# RH025_1.net
KiCad netlist of a schematic drawn in EAGLE
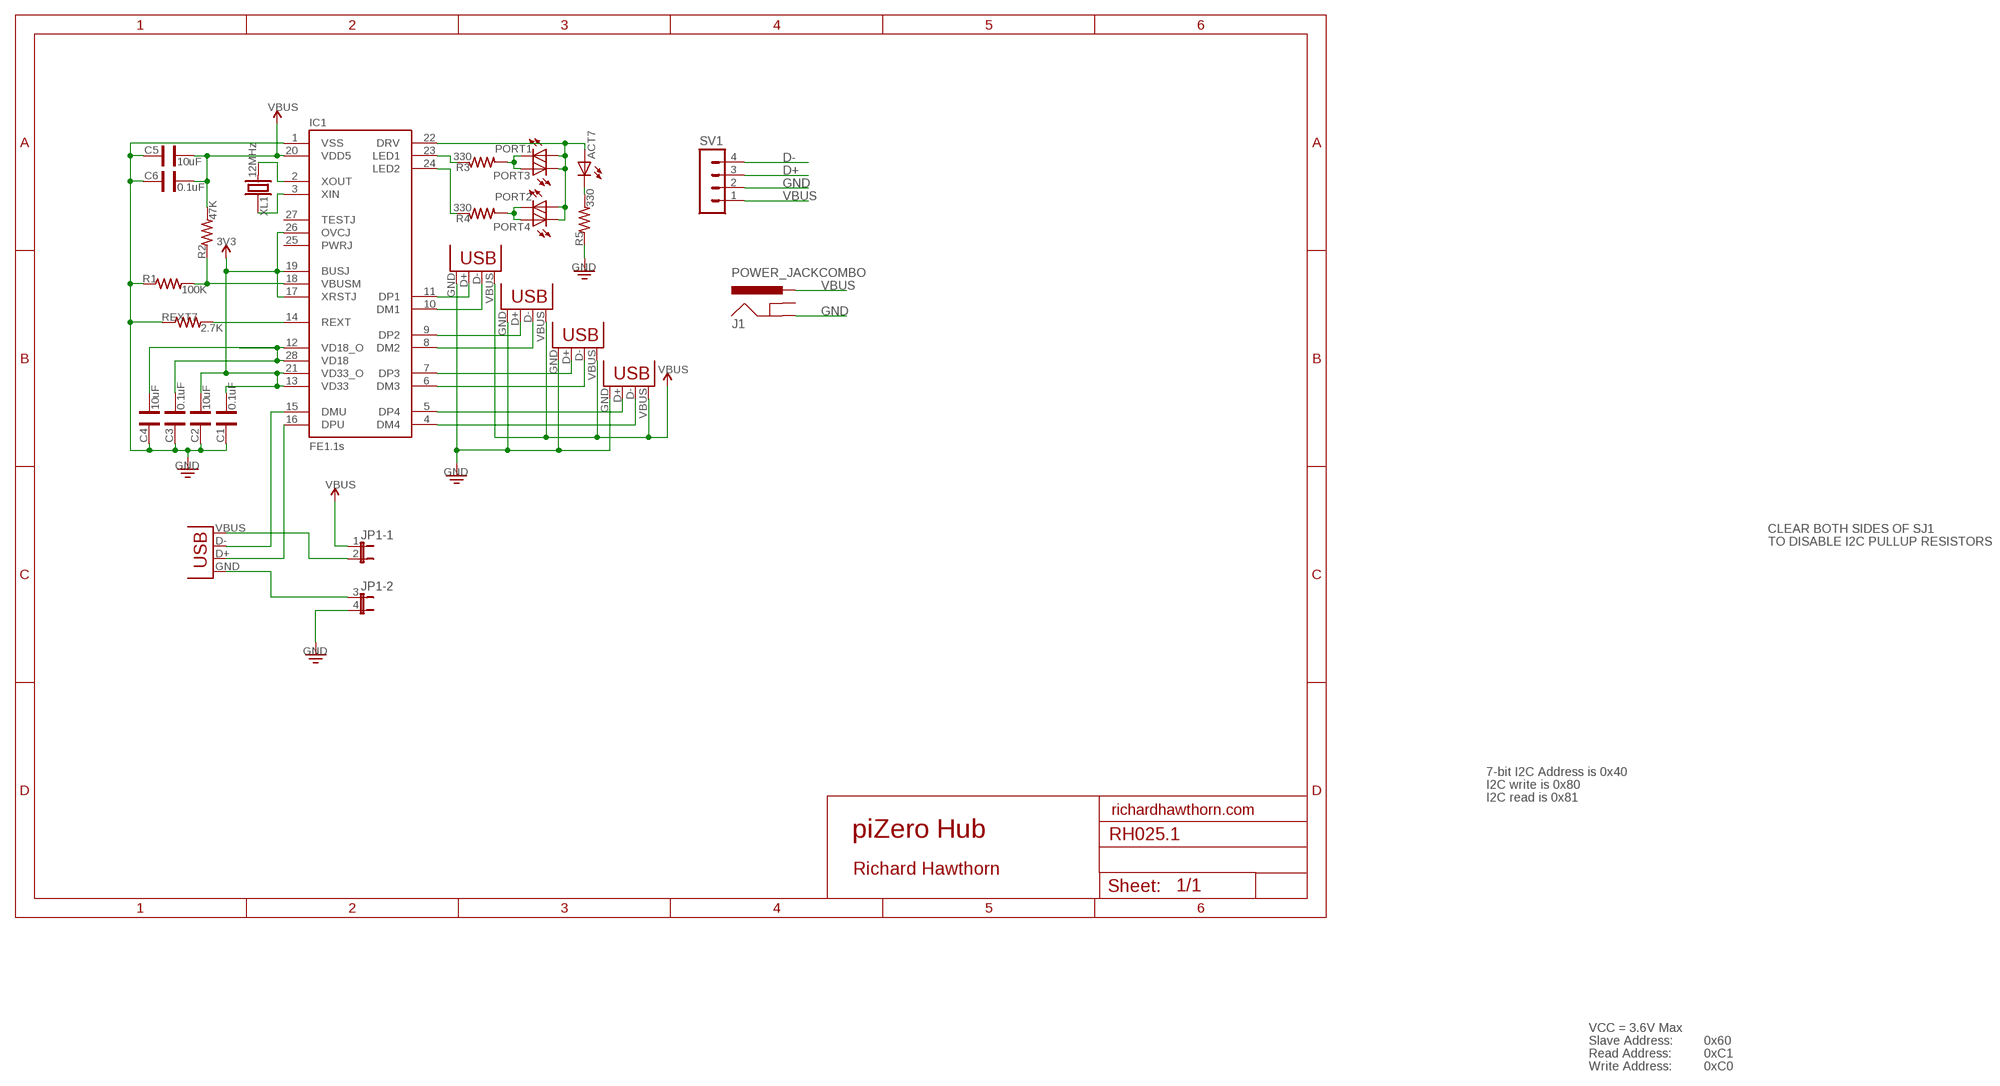
[diagram p0: schematic, sheet 1]

(export (version "E")
  (design (tool "Eeschema 10.0.6"))
  (components
    (comp (ref "ACT7")
      (value "LED0603")
      (footprint "eagle-import:LED-0603")
      (libsource (lib "eagle-import") (part "LED0603"))
    )
    (comp (ref "C1")
      (value "0.1uF")
      (footprint "eagle-import:CAP-0603")
      (libsource (lib "eagle-import") (part "CAP0603"))
    )
    (comp (ref "C2")
      (value "10uF")
      (footprint "eagle-import:CAP-0603")
      (libsource (lib "eagle-import") (part "CAP0603"))
    )
    (comp (ref "C3")
      (value "0.1uF")
      (footprint "eagle-import:CAP-0603")
      (libsource (lib "eagle-import") (part "CAP0603"))
    )
    (comp (ref "C4")
      (value "10uF")
      (footprint "eagle-import:CAP-0603")
      (libsource (lib "eagle-import") (part "CAP0603"))
    )
    (comp (ref "C5")
      (value "10uF")
      (footprint "eagle-import:CAP-0603")
      (libsource (lib "eagle-import") (part "CAP0603"))
    )
    (comp (ref "C6")
      (value "0.1uF")
      (footprint "eagle-import:CAP-0603")
      (libsource (lib "eagle-import") (part "CAP0603"))
    )
    (comp (ref "IC1")
      (value "FE1.1S")
      (footprint "eagle-import:FE1.1S_SSOP-28")
      (libsource (lib "eagle-import") (part "FE1.1S"))
    )
    (comp (ref "J1")
      (value "POWER_JACKCOMBO")
      (footprint "eagle-import:POWER_JACK_COMBO")
      (libsource (lib "eagle-import") (part "POWER_JACKCOMBO"))
    )
    (comp (ref "JP1")
      (value "JP2QE")
      (footprint "eagle-import:JP2Q")
      (libsource (lib "eagle-import") (part "JP2QE"))
    )
    (comp (ref "PORT1")
      (value "LED0603")
      (footprint "eagle-import:LED-0603")
      (libsource (lib "eagle-import") (part "LED0603"))
    )
    (comp (ref "PORT2")
      (value "LED0603")
      (footprint "eagle-import:LED-0603")
      (libsource (lib "eagle-import") (part "LED0603"))
    )
    (comp (ref "PORT3")
      (value "LED0603")
      (footprint "eagle-import:LED-0603")
      (libsource (lib "eagle-import") (part "LED0603"))
    )
    (comp (ref "PORT4")
      (value "LED0603")
      (footprint "eagle-import:LED-0603")
      (libsource (lib "eagle-import") (part "LED0603"))
    )
    (comp (ref "R1")
      (value "100K")
      (footprint "eagle-import:RES-0603")
      (libsource (lib "eagle-import") (part "RES0603"))
    )
    (comp (ref "R2")
      (value "47K")
      (footprint "eagle-import:RES-0603")
      (libsource (lib "eagle-import") (part "RES0603"))
    )
    (comp (ref "R3")
      (value "330")
      (footprint "eagle-import:RES-0603")
      (libsource (lib "eagle-import") (part "RES0603"))
    )
    (comp (ref "R4")
      (value "330")
      (footprint "eagle-import:RES-0603")
      (libsource (lib "eagle-import") (part "RES0603"))
    )
    (comp (ref "R5")
      (value "330")
      (footprint "eagle-import:RES-0603")
      (libsource (lib "eagle-import") (part "RES0603"))
    )
    (comp (ref "REXT7")
      (value "2.7K")
      (footprint "eagle-import:RES-0603")
      (libsource (lib "eagle-import") (part "RES0603"))
    )
    (comp (ref "SV1")
      (value "MA04-1")
      (footprint "eagle-import:MA04-1")
      (libsource (lib "eagle-import") (part "MA04-1"))
    )
    (comp (ref "USB1")
      (value "USBMICROB-PTH")
      (footprint "eagle-import:USB-MICROB-TH")
      (libsource (lib "eagle-import") (part "USBMICROB-PTH"))
    )
    (comp (ref "USB2")
      (value "USBA-PTH")
      (footprint "eagle-import:USB-A-F-PTH")
      (libsource (lib "eagle-import") (part "USBA-PTH"))
    )
    (comp (ref "USB3")
      (value "USBA-PTH")
      (footprint "eagle-import:USB-A-F-PTH")
      (libsource (lib "eagle-import") (part "USBA-PTH"))
    )
    (comp (ref "USB4")
      (value "USBA-PTH")
      (footprint "eagle-import:USB-A-F-PTH")
      (libsource (lib "eagle-import") (part "USBA-PTH"))
    )
    (comp (ref "USB5")
      (value "USBA-PTH")
      (footprint "eagle-import:USB-A-F-PTH")
      (libsource (lib "eagle-import") (part "USBA-PTH"))
    )
    (comp (ref "XL1")
      (value "12MHz")
      (footprint "eagle-import:HC49UP")
      (libsource (lib "eagle-import") (part "CRYSTALHC49UP"))
    )
  )
  (nets
    (net (code "1") (name "/D+") (class "Default")
      (node (ref "IC1") (pin "16") (pinfunction "DPU_16") (pintype "bidirectional"))
      (node (ref "SV1") (pin "3") (pinfunction "3_3") (pintype "passive"))
      (node (ref "USB1") (pin "D+") (pinfunction "D+_D+") (pintype "bidirectional"))
    )
    (net (code "2") (name "/D-") (class "Default")
      (node (ref "IC1") (pin "15") (pinfunction "DMU_15") (pintype "bidirectional"))
      (node (ref "SV1") (pin "4") (pinfunction "4_4") (pintype "passive"))
      (node (ref "USB1") (pin "D-") (pinfunction "D-_D-") (pintype "bidirectional"))
    )
    (net (code "3") (name "3V3") (class "Default")
      (node (ref "C1") (pin "1") (pinfunction "1_1") (pintype "passive"))
      (node (ref "C2") (pin "1") (pinfunction "1_1") (pintype "passive"))
      (node (ref "IC1") (pin "13") (pinfunction "VD33_13") (pintype "bidirectional"))
      (node (ref "IC1") (pin "17") (pinfunction "XRSTJ_17") (pintype "bidirectional"))
      (node (ref "IC1") (pin "19") (pinfunction "BUSJ_19") (pintype "bidirectional"))
      (node (ref "IC1") (pin "21") (pinfunction "VD33_O_21") (pintype "bidirectional"))
      (node (ref "IC1") (pin "26") (pinfunction "OVCJ_26") (pintype "bidirectional"))
    )
    (net (code "4") (name "GND") (class "Default")
      (node (ref "C1") (pin "2") (pinfunction "2_2") (pintype "passive"))
      (node (ref "C2") (pin "2") (pinfunction "2_2") (pintype "passive"))
      (node (ref "C3") (pin "2") (pinfunction "2_2") (pintype "passive"))
      (node (ref "C4") (pin "2") (pinfunction "2_2") (pintype "passive"))
      (node (ref "C5") (pin "2") (pinfunction "2_2") (pintype "passive"))
      (node (ref "C6") (pin "2") (pinfunction "2_2") (pintype "passive"))
      (node (ref "IC1") (pin "1") (pinfunction "VSS_1") (pintype "bidirectional"))
      (node (ref "J1") (pin "GND@1") (pinfunction "GND_GND@1") (pintype "bidirectional"))
      (node (ref "JP1") (pin "4") (pinfunction "2_4") (pintype "passive"))
      (node (ref "R1") (pin "1") (pinfunction "1_1") (pintype "passive"))
      (node (ref "R5") (pin "1") (pinfunction "1_1") (pintype "passive"))
      (node (ref "REXT7") (pin "1") (pinfunction "1_1") (pintype "passive"))
      (node (ref "SV1") (pin "2") (pinfunction "2_2") (pintype "passive"))
      (node (ref "USB2") (pin "GND") (pinfunction "GND_GND") (pintype "bidirectional"))
      (node (ref "USB3") (pin "GND") (pinfunction "GND_GND") (pintype "bidirectional"))
      (node (ref "USB4") (pin "GND") (pinfunction "GND_GND") (pintype "bidirectional"))
      (node (ref "USB5") (pin "GND") (pinfunction "GND_GND") (pintype "bidirectional"))
    )
    (net (code "5") (name "Net-(ACT7-PadC)") (class "Default")
      (node (ref "ACT7") (pin "C") (pinfunction "C_C") (pintype "passive"))
      (node (ref "R5") (pin "2") (pinfunction "2_2") (pintype "passive"))
    )
    (net (code "6") (name "Net-(IC1-DM1)") (class "Default")
      (node (ref "IC1") (pin "10") (pinfunction "DM1_10") (pintype "bidirectional"))
      (node (ref "USB5") (pin "D-") (pinfunction "D-_D-") (pintype "bidirectional"))
    )
    (net (code "7") (name "Net-(IC1-DM2)") (class "Default")
      (node (ref "IC1") (pin "8") (pinfunction "DM2_8") (pintype "bidirectional"))
      (node (ref "USB4") (pin "D-") (pinfunction "D-_D-") (pintype "bidirectional"))
    )
    (net (code "8") (name "Net-(IC1-DM3)") (class "Default")
      (node (ref "IC1") (pin "6") (pinfunction "DM3_6") (pintype "bidirectional"))
      (node (ref "USB3") (pin "D-") (pinfunction "D-_D-") (pintype "bidirectional"))
    )
    (net (code "9") (name "Net-(IC1-DM4)") (class "Default")
      (node (ref "IC1") (pin "4") (pinfunction "DM4_4") (pintype "bidirectional"))
      (node (ref "USB2") (pin "D-") (pinfunction "D-_D-") (pintype "bidirectional"))
    )
    (net (code "10") (name "Net-(IC1-DP1)") (class "Default")
      (node (ref "IC1") (pin "11") (pinfunction "DP1_11") (pintype "bidirectional"))
      (node (ref "USB5") (pin "D+") (pinfunction "D+_D+") (pintype "bidirectional"))
    )
    (net (code "11") (name "Net-(IC1-DP2)") (class "Default")
      (node (ref "IC1") (pin "9") (pinfunction "DP2_9") (pintype "bidirectional"))
      (node (ref "USB4") (pin "D+") (pinfunction "D+_D+") (pintype "bidirectional"))
    )
    (net (code "12") (name "Net-(IC1-DP3)") (class "Default")
      (node (ref "IC1") (pin "7") (pinfunction "DP3_7") (pintype "bidirectional"))
      (node (ref "USB3") (pin "D+") (pinfunction "D+_D+") (pintype "bidirectional"))
    )
    (net (code "13") (name "Net-(IC1-DP4)") (class "Default")
      (node (ref "IC1") (pin "5") (pinfunction "DP4_5") (pintype "bidirectional"))
      (node (ref "USB2") (pin "D+") (pinfunction "D+_D+") (pintype "bidirectional"))
    )
    (net (code "14") (name "Net-(IC1-DRV)") (class "Default")
      (node (ref "ACT7") (pin "A") (pinfunction "A_A") (pintype "passive"))
      (node (ref "IC1") (pin "22") (pinfunction "DRV_22") (pintype "bidirectional"))
      (node (ref "PORT1") (pin "A") (pinfunction "A_A") (pintype "passive"))
      (node (ref "PORT2") (pin "A") (pinfunction "A_A") (pintype "passive"))
      (node (ref "PORT3") (pin "C") (pinfunction "C_C") (pintype "passive"))
      (node (ref "PORT4") (pin "C") (pinfunction "C_C") (pintype "passive"))
    )
    (net (code "15") (name "Net-(IC1-LED1)") (class "Default")
      (node (ref "IC1") (pin "23") (pinfunction "LED1_23") (pintype "bidirectional"))
      (node (ref "R3") (pin "1") (pinfunction "1_1") (pintype "passive"))
    )
    (net (code "16") (name "Net-(IC1-LED2)") (class "Default")
      (node (ref "IC1") (pin "24") (pinfunction "LED2_24") (pintype "bidirectional"))
      (node (ref "R4") (pin "1") (pinfunction "1_1") (pintype "passive"))
    )
    (net (code "17") (name "Net-(IC1-REXT)") (class "Default")
      (node (ref "IC1") (pin "14") (pinfunction "REXT_14") (pintype "bidirectional"))
      (node (ref "REXT7") (pin "2") (pinfunction "2_2") (pintype "passive"))
    )
    (net (code "18") (name "Net-(IC1-VBUSM)") (class "Default")
      (node (ref "IC1") (pin "18") (pinfunction "VBUSM_18") (pintype "bidirectional"))
      (node (ref "R1") (pin "2") (pinfunction "2_2") (pintype "passive"))
      (node (ref "R2") (pin "1") (pinfunction "1_1") (pintype "passive"))
    )
    (net (code "19") (name "Net-(IC1-VD18)") (class "Default")
      (node (ref "C3") (pin "1") (pinfunction "1_1") (pintype "passive"))
      (node (ref "C4") (pin "1") (pinfunction "1_1") (pintype "passive"))
      (node (ref "IC1") (pin "12") (pinfunction "VD18_O_12") (pintype "bidirectional"))
      (node (ref "IC1") (pin "28") (pinfunction "VD18_28") (pintype "bidirectional"))
    )
    (net (code "20") (name "Net-(IC1-XIN)") (class "Default")
      (node (ref "IC1") (pin "3") (pinfunction "XIN_3") (pintype "bidirectional"))
      (node (ref "XL1") (pin "1") (pinfunction "1_1") (pintype "passive"))
    )
    (net (code "21") (name "Net-(IC1-XOUT)") (class "Default")
      (node (ref "IC1") (pin "2") (pinfunction "XOUT_2") (pintype "bidirectional"))
      (node (ref "XL1") (pin "2") (pinfunction "2_2") (pintype "passive"))
    )
    (net (code "22") (name "Net-(JP1-Pad2)") (class "Default")
      (node (ref "JP1") (pin "2") (pinfunction "2_2") (pintype "passive"))
      (node (ref "USB1") (pin "VBUS") (pinfunction "VBUS_VBUS") (pintype "bidirectional"))
    )
    (net (code "23") (name "Net-(JP1B-1)") (class "Default")
      (node (ref "JP1") (pin "3") (pinfunction "1_3") (pintype "passive"))
      (node (ref "USB1") (pin "GND") (pinfunction "GND_GND") (pintype "bidirectional"))
    )
    (net (code "24") (name "Net-(PORT1-PadC)") (class "Default")
      (node (ref "PORT1") (pin "C") (pinfunction "C_C") (pintype "passive"))
      (node (ref "PORT3") (pin "A") (pinfunction "A_A") (pintype "passive"))
      (node (ref "R3") (pin "2") (pinfunction "2_2") (pintype "passive"))
    )
    (net (code "25") (name "Net-(PORT2-PadC)") (class "Default")
      (node (ref "PORT2") (pin "C") (pinfunction "C_C") (pintype "passive"))
      (node (ref "PORT4") (pin "A") (pinfunction "A_A") (pintype "passive"))
      (node (ref "R4") (pin "2") (pinfunction "2_2") (pintype "passive"))
    )
    (net (code "26") (name "VBUS") (class "Default")
      (node (ref "C5") (pin "1") (pinfunction "1_1") (pintype "passive"))
      (node (ref "C6") (pin "1") (pinfunction "1_1") (pintype "passive"))
      (node (ref "IC1") (pin "20") (pinfunction "VDD5_20") (pintype "bidirectional"))
      (node (ref "J1") (pin "POWER") (pinfunction "PWR_POWER") (pintype "bidirectional"))
      (node (ref "JP1") (pin "1") (pinfunction "1_1") (pintype "passive"))
      (node (ref "R2") (pin "2") (pinfunction "2_2") (pintype "passive"))
      (node (ref "SV1") (pin "1") (pinfunction "1_1") (pintype "passive"))
      (node (ref "USB2") (pin "VBUS") (pinfunction "VBUS_VBUS") (pintype "bidirectional"))
      (node (ref "USB3") (pin "VBUS") (pinfunction "VBUS_VBUS") (pintype "bidirectional"))
      (node (ref "USB4") (pin "VBUS") (pinfunction "VBUS_VBUS") (pintype "bidirectional"))
      (node (ref "USB5") (pin "VBUS") (pinfunction "VBUS_VBUS") (pintype "bidirectional"))
    )
    (net (code "27") (name "unconnected-(IC1-PWRJ-Pad25)") (class "Default")
      (node (ref "IC1") (pin "25") (pinfunction "PWRJ_25") (pintype "bidirectional"))
    )
    (net (code "28") (name "unconnected-(IC1-TESTJ-Pad27)") (class "Default")
      (node (ref "IC1") (pin "27") (pinfunction "TESTJ_27") (pintype "bidirectional"))
    )
    (net (code "29") (name "unconnected-(J1-GNDBREAK-PadGND)") (class "Default")
      (node (ref "J1") (pin "GND") (pinfunction "GNDBREAK_GND") (pintype "bidirectional"))
    )
  )
)
